# keyboard_v2.net
KiCad netlist of a schematic drawn in EAGLE
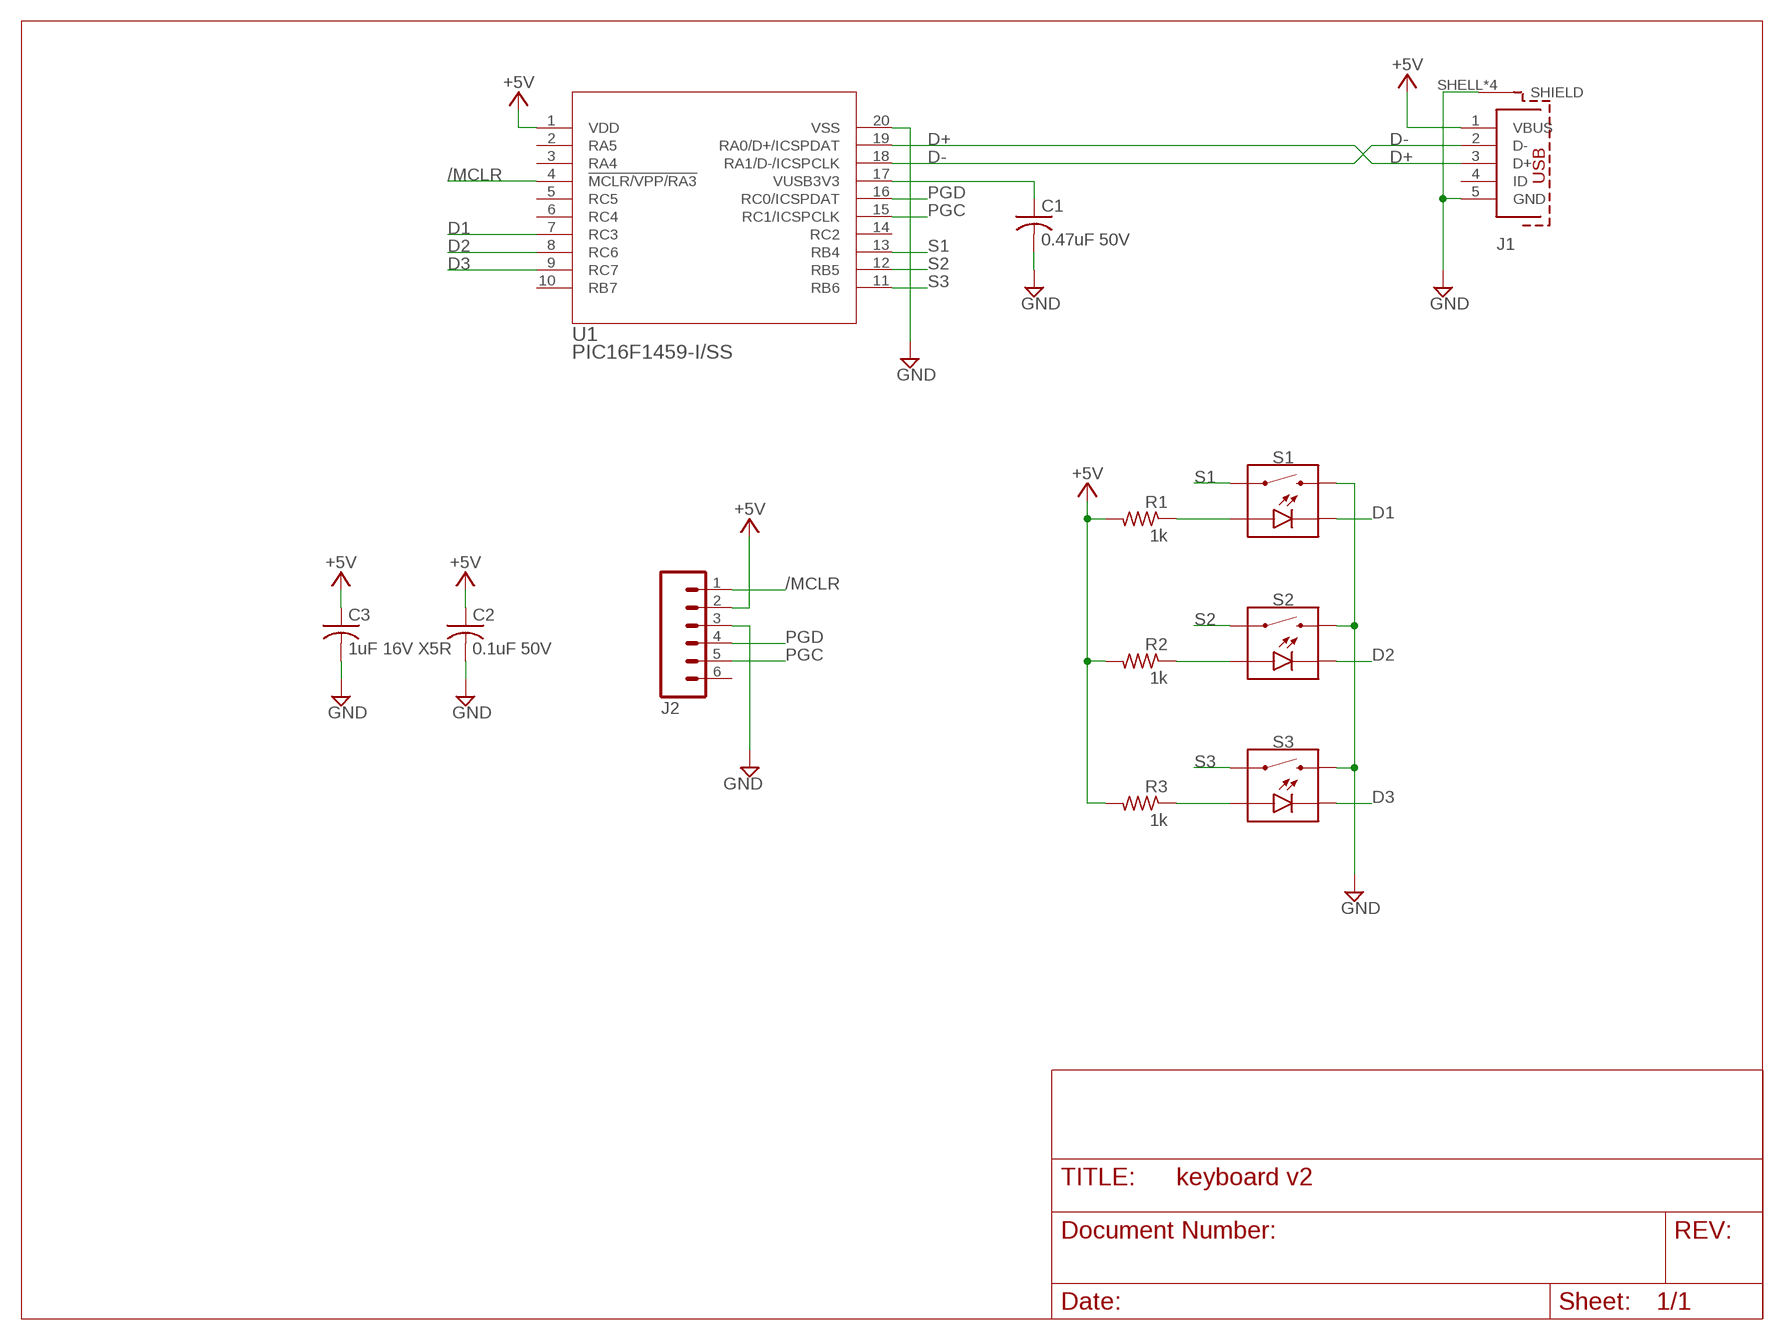
[diagram p0: schematic, sheet 1]

(export (version "E")
  (design (tool "Eeschema 10.0.6"))
  (components
    (comp (ref "C1")
      (value "0.47uF 50V")
      (footprint "eagle-import:C1206K")
      (fields (field (name "MFR") "KEMET") (field (name "MFR_PART_NO") "C1206C474K5RACTU"))
      (libsource (lib "eagle-import") (part "C-USC1206K"))
    )
    (comp (ref "C2")
      (value "0.1uF 50V")
      (footprint "eagle-import:C1206K")
      (fields (field (name "MFR") "KEMET") (field (name "MFR_PART_NO") "C1206S104M5RACTU"))
      (libsource (lib "eagle-import") (part "C-USC1206K"))
    )
    (comp (ref "C3")
      (value "1uF 16V X5R")
      (footprint "eagle-import:C1210")
      (fields (field (name "MFR") "KEMET") (field (name "MFR_PART_NO") "C1210C105K4PACTU"))
      (libsource (lib "eagle-import") (part "C-USC1210"))
    )
    (comp (ref "J1")
      (value "629105136821")
      (footprint "eagle-import:629105136821")
      (libsource (lib "eagle-import") (part "629105136821"))
    )
    (comp (ref "J2")
      (value "M06SIP")
      (footprint "eagle-import:1X06")
      (libsource (lib "eagle-import") (part "M06SIP"))
    )
    (comp (ref "R1")
      (value "1k")
      (footprint "eagle-import:R1206")
      (fields (field (name "MFR") "BOURNS") (field (name "MFR_PART_NO") "CR1206-JW-102ELF"))
      (libsource (lib "eagle-import") (part "R-US_R1206"))
    )
    (comp (ref "R2")
      (value "1k")
      (footprint "eagle-import:R1206")
      (fields (field (name "MFR") "BOURNS") (field (name "MFR_PART_NO") "CR1206-JW-102ELF"))
      (libsource (lib "eagle-import") (part "R-US_R1206"))
    )
    (comp (ref "R3")
      (value "1k")
      (footprint "eagle-import:R1206")
      (fields (field (name "MFR") "BOURNS") (field (name "MFR_PART_NO") "CR1206-JW-102ELF"))
      (libsource (lib "eagle-import") (part "R-US_R1206"))
    )
    (comp (ref "S1")
      (value "MOMENTARY-SWITCH-SPST-LED-PTH-CHERRY")
      (footprint "eagle-import:CHERRY-MX-LED")
      (libsource (lib "eagle-import") (part "MOMENTARY-SWITCH-SPST-LED-PTH-CHERRY"))
    )
    (comp (ref "S2")
      (value "MOMENTARY-SWITCH-SPST-LED-PTH-CHERRY")
      (footprint "eagle-import:CHERRY-MX-LED")
      (libsource (lib "eagle-import") (part "MOMENTARY-SWITCH-SPST-LED-PTH-CHERRY"))
    )
    (comp (ref "S3")
      (value "MOMENTARY-SWITCH-SPST-LED-PTH-CHERRY")
      (footprint "eagle-import:CHERRY-MX-LED")
      (libsource (lib "eagle-import") (part "MOMENTARY-SWITCH-SPST-LED-PTH-CHERRY"))
    )
    (comp (ref "U1")
      (value "PIC16F1459-I/SS")
      (footprint "eagle-import:SSOP20_MC")
      (fields (field (name "MANUFACTURER_PART_NUMBER") "PIC16F1459ISS"))
      (libsource (lib "eagle-import") (part "PIC16F1459-I/SS"))
    )
  )
  (nets
    (net (code "1") (name "+5V") (class "Default")
      (node (ref "C2") (pin "1") (pinfunction "1_1") (pintype "passive"))
      (node (ref "C3") (pin "1") (pinfunction "1_1") (pintype "passive"))
      (node (ref "J1") (pin "1") (pinfunction "VBUS_1") (pintype "passive"))
      (node (ref "J2") (pin "2") (pinfunction "2_2") (pintype "passive"))
      (node (ref "R1") (pin "2") (pinfunction "2_2") (pintype "passive"))
      (node (ref "R2") (pin "2") (pinfunction "2_2") (pintype "passive"))
      (node (ref "R3") (pin "2") (pinfunction "2_2") (pintype "passive"))
      (node (ref "U1") (pin "1") (pinfunction "VDD_1") (pintype "power_in"))
    )
    (net (code "2") (name "/D+") (class "Default")
      (node (ref "J1") (pin "3") (pinfunction "D+_3") (pintype "passive"))
      (node (ref "U1") (pin "19") (pinfunction "RA0/D+/ICSPDAT_19") (pintype "bidirectional"))
    )
    (net (code "3") (name "/D-") (class "Default")
      (node (ref "J1") (pin "2") (pinfunction "D-_2") (pintype "passive"))
      (node (ref "U1") (pin "18") (pinfunction "RA1/D-/ICSPCLK_18") (pintype "bidirectional"))
    )
    (net (code "4") (name "/D1") (class "Default")
      (node (ref "S1") (pin "K") (pinfunction "C_K") (pintype "passive"))
      (node (ref "U1") (pin "7") (pinfunction "RC3_7") (pintype "bidirectional"))
    )
    (net (code "5") (name "/D2") (class "Default")
      (node (ref "S2") (pin "K") (pinfunction "C_K") (pintype "passive"))
      (node (ref "U1") (pin "8") (pinfunction "RC6_8") (pintype "bidirectional"))
    )
    (net (code "6") (name "/D3") (class "Default")
      (node (ref "S3") (pin "K") (pinfunction "C_K") (pintype "passive"))
      (node (ref "U1") (pin "9") (pinfunction "RC7_9") (pintype "bidirectional"))
    )
    (net (code "7") (name "/PGC") (class "Default")
      (node (ref "J2") (pin "5") (pinfunction "5_5") (pintype "passive"))
      (node (ref "U1") (pin "15") (pinfunction "RC1/ICSPCLK_15") (pintype "bidirectional"))
    )
    (net (code "8") (name "/PGD") (class "Default")
      (node (ref "J2") (pin "4") (pinfunction "4_4") (pintype "passive"))
      (node (ref "U1") (pin "16") (pinfunction "RC0/ICSPDAT_16") (pintype "bidirectional"))
    )
    (net (code "9") (name "/S1") (class "Default")
      (node (ref "S1") (pin "S1") (pinfunction "1_S1") (pintype "passive"))
      (node (ref "U1") (pin "13") (pinfunction "RB4_13") (pintype "bidirectional"))
    )
    (net (code "10") (name "/S2") (class "Default")
      (node (ref "S2") (pin "S1") (pinfunction "1_S1") (pintype "passive"))
      (node (ref "U1") (pin "12") (pinfunction "RB5_12") (pintype "bidirectional"))
    )
    (net (code "11") (name "/S3") (class "Default")
      (node (ref "S3") (pin "S1") (pinfunction "1_S1") (pintype "passive"))
      (node (ref "U1") (pin "11") (pinfunction "RB6_11") (pintype "bidirectional"))
    )
    (net (code "12") (name "/{slash}MCLR") (class "Default")
      (node (ref "J2") (pin "1") (pinfunction "1_1") (pintype "passive"))
      (node (ref "U1") (pin "4") (pinfunction "~{MCLR/VPP/RA3}_4") (pintype "bidirectional"))
    )
    (net (code "13") (name "GND") (class "Default")
      (node (ref "C1") (pin "2") (pinfunction "2_2") (pintype "passive"))
      (node (ref "C2") (pin "2") (pinfunction "2_2") (pintype "passive"))
      (node (ref "C3") (pin "2") (pinfunction "2_2") (pintype "passive"))
      (node (ref "J1") (pin "5") (pinfunction "GND_5") (pintype "passive"))
      (node (ref "J1") (pin "SHELL") (pinfunction "SHIELD_SHELL") (pintype "passive"))
      (node (ref "J1") (pin "SHELL1") (pinfunction "SHIELD_SHELL1") (pintype "passive"))
      (node (ref "J1") (pin "SHELL2") (pinfunction "SHIELD_SHELL2") (pintype "passive"))
      (node (ref "J1") (pin "SHELL3") (pinfunction "SHIELD_SHELL3") (pintype "passive"))
      (node (ref "J2") (pin "3") (pinfunction "3_3") (pintype "passive"))
      (node (ref "S1") (pin "S2") (pinfunction "2_S2") (pintype "passive"))
      (node (ref "S2") (pin "S2") (pinfunction "2_S2") (pintype "passive"))
      (node (ref "S3") (pin "S2") (pinfunction "2_S2") (pintype "passive"))
      (node (ref "U1") (pin "20") (pinfunction "VSS_20") (pintype "power_in"))
    )
    (net (code "14") (name "Net-(R1-Pad1)") (class "Default")
      (node (ref "R1") (pin "1") (pinfunction "1_1") (pintype "passive"))
      (node (ref "S1") (pin "A") (pinfunction "A_A") (pintype "passive"))
    )
    (net (code "15") (name "Net-(R2-Pad1)") (class "Default")
      (node (ref "R2") (pin "1") (pinfunction "1_1") (pintype "passive"))
      (node (ref "S2") (pin "A") (pinfunction "A_A") (pintype "passive"))
    )
    (net (code "16") (name "Net-(R3-Pad1)") (class "Default")
      (node (ref "R3") (pin "1") (pinfunction "1_1") (pintype "passive"))
      (node (ref "S3") (pin "A") (pinfunction "A_A") (pintype "passive"))
    )
    (net (code "17") (name "Net-(U1-VUSB3V3)") (class "Default")
      (node (ref "C1") (pin "1") (pinfunction "1_1") (pintype "passive"))
      (node (ref "U1") (pin "17") (pinfunction "VUSB3V3_17") (pintype "power_in"))
    )
    (net (code "18") (name "unconnected-(J1-ID-Pad4)") (class "Default")
      (node (ref "J1") (pin "4") (pinfunction "ID_4") (pintype "passive"))
    )
    (net (code "19") (name "unconnected-(J2-Pad6)") (class "Default")
      (node (ref "J2") (pin "6") (pinfunction "6_6") (pintype "passive"))
    )
    (net (code "20") (name "unconnected-(U1-RA4-Pad3)") (class "Default")
      (node (ref "U1") (pin "3") (pinfunction "RA4_3") (pintype "bidirectional"))
    )
    (net (code "21") (name "unconnected-(U1-RA5-Pad2)") (class "Default")
      (node (ref "U1") (pin "2") (pinfunction "RA5_2") (pintype "bidirectional"))
    )
    (net (code "22") (name "unconnected-(U1-RB7-Pad10)") (class "Default")
      (node (ref "U1") (pin "10") (pinfunction "RB7_10") (pintype "bidirectional"))
    )
    (net (code "23") (name "unconnected-(U1-RC2-Pad14)") (class "Default")
      (node (ref "U1") (pin "14") (pinfunction "RC2_14") (pintype "bidirectional"))
    )
    (net (code "24") (name "unconnected-(U1-RC4-Pad6)") (class "Default")
      (node (ref "U1") (pin "6") (pinfunction "RC4_6") (pintype "bidirectional"))
    )
    (net (code "25") (name "unconnected-(U1-RC5-Pad5)") (class "Default")
      (node (ref "U1") (pin "5") (pinfunction "RC5_5") (pintype "bidirectional"))
    )
  )
)
